# Hypnos_V2_2_24.net
KiCad netlist of a schematic drawn in EAGLE
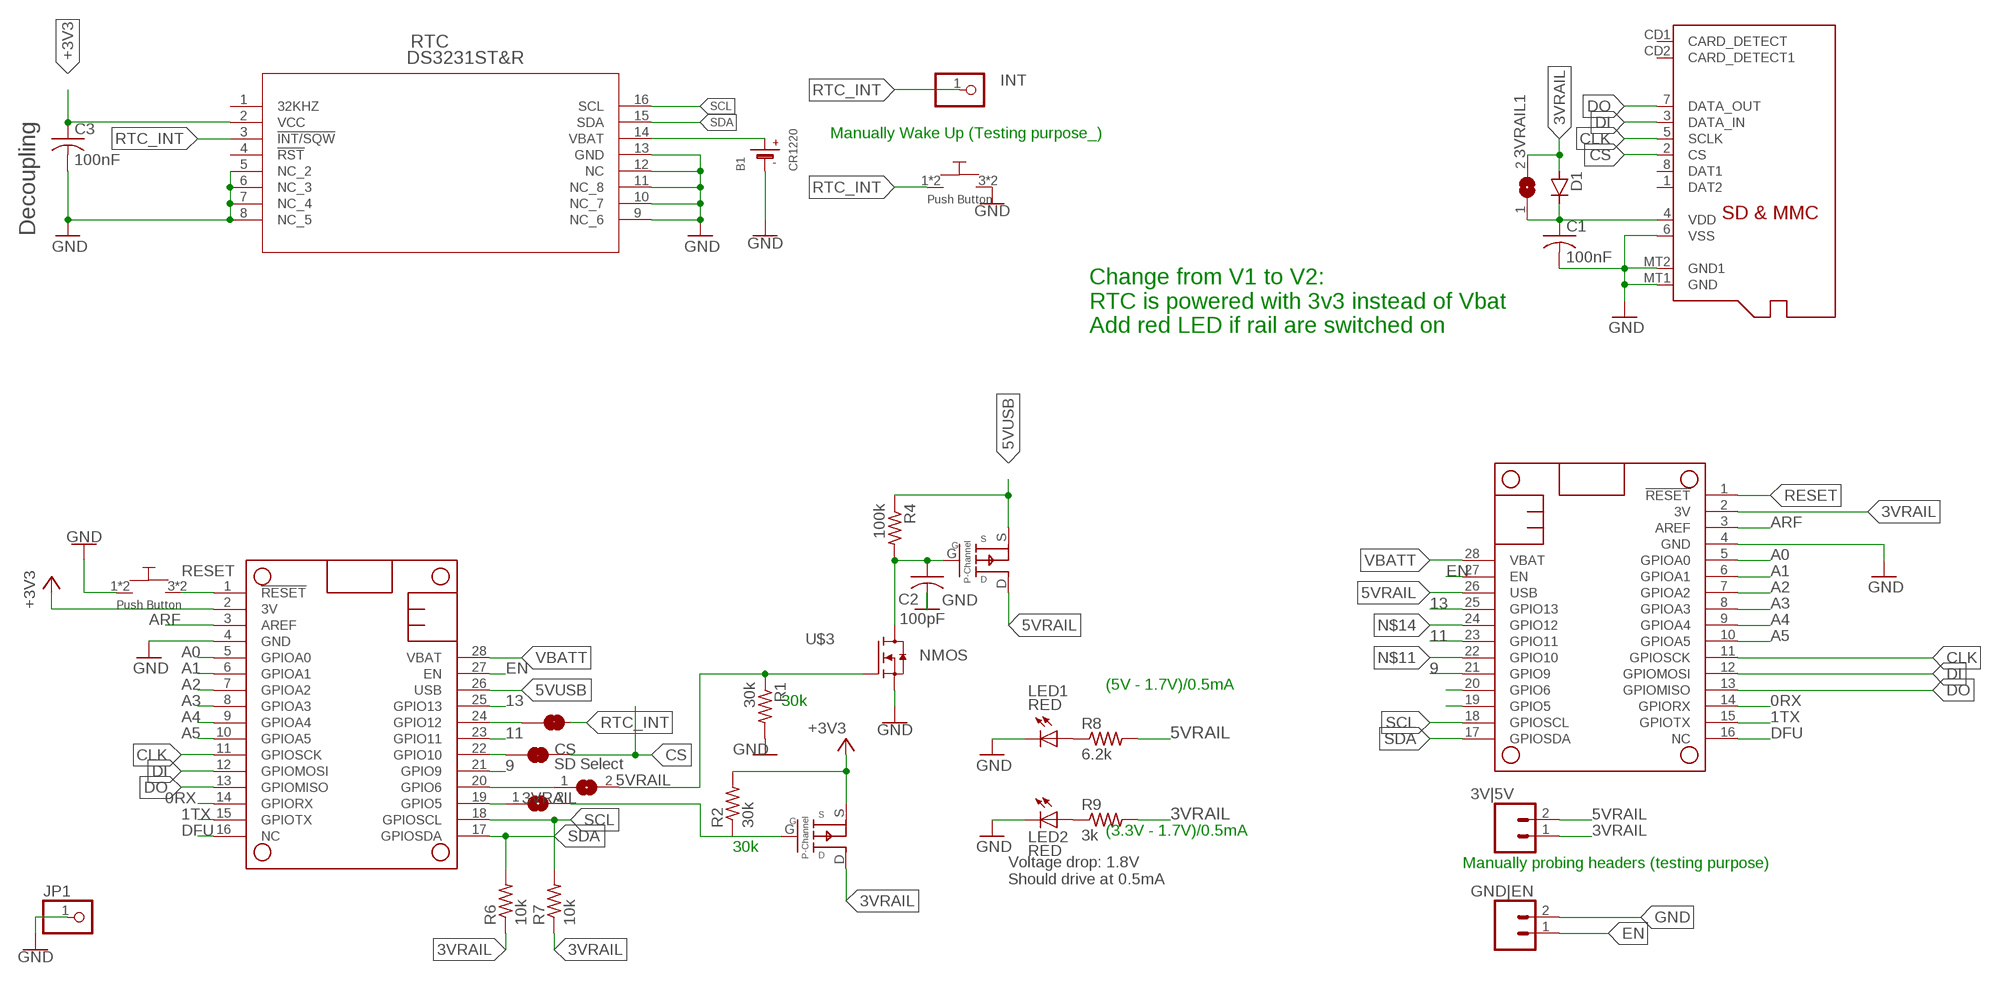
[diagram p0: schematic, sheet 1]

(export (version "E")
  (design (tool "Eeschema 10.0.6"))
  (components
    (comp (ref "3VRAIL")
      (value "SJ")
      (footprint "eagle-import:SJ")
      (libsource (lib "eagle-import") (part "SJ"))
    )
    (comp (ref "3VRAIL1")
      (value "SJ")
      (footprint "eagle-import:SJ")
      (libsource (lib "eagle-import") (part "SJ"))
    )
    (comp (ref "3V|5V")
      (value "CONN_021X02_NO_SILK")
      (footprint "eagle-import:1X02_NO_SILK")
      (libsource (lib "eagle-import") (part "CONN_021X02_NO_SILK"))
    )
    (comp (ref "5VRAIL")
      (value "SJ")
      (footprint "eagle-import:SJ")
      (libsource (lib "eagle-import") (part "SJ"))
    )
    (comp (ref "B1")
      (value "CR1220")
      (footprint "eagle-import:CR1220")
      (libsource (lib "eagle-import") (part "BATTERYCR1220_SMT"))
    )
    (comp (ref "C1")
      (value "100nF")
      (footprint "eagle-import:C1206")
      (libsource (lib "eagle-import") (part "C-USC1206"))
    )
    (comp (ref "C2")
      (value "100pF")
      (footprint "eagle-import:C0805")
      (libsource (lib "eagle-import") (part "C-USC0805"))
    )
    (comp (ref "C3")
      (value "100nF")
      (footprint "eagle-import:C1206")
      (libsource (lib "eagle-import") (part "C-USC1206"))
    )
    (comp (ref "CS")
      (value "SD Select")
      (footprint "eagle-import:SMT-JUMPER_2_NC_TRACE_SILK")
      (libsource (lib "eagle-import") (part "JUMPER-SMT_2_NC_TRACE_SILK"))
    )
    (comp (ref "D1")
      (value "D-SOD123")
      (footprint "eagle-import:SOD123")
      (libsource (lib "eagle-import") (part "D-SOD123"))
    )
    (comp (ref "GND|EN")
      (value "CONN_021X02_NO_SILK")
      (footprint "eagle-import:1X02_NO_SILK")
      (libsource (lib "eagle-import") (part "CONN_021X02_NO_SILK"))
    )
    (comp (ref "INT")
      (value "PINHD-1X1CB")
      (footprint "eagle-import:1X01-CLEANBIG")
      (libsource (lib "eagle-import") (part "PINHD-1X1CB"))
    )
    (comp (ref "JP1")
      (value "PINHD-1X1CB")
      (footprint "eagle-import:1X01-CLEANBIG")
      (libsource (lib "eagle-import") (part "PINHD-1X1CB"))
    )
    (comp (ref "LED1")
      (value "RED")
      (footprint "eagle-import:CHIPLED_0805")
      (libsource (lib "eagle-import") (part "LEDCHIPLED_0805"))
    )
    (comp (ref "LED2")
      (value "RED")
      (footprint "eagle-import:CHIPLED_0805")
      (libsource (lib "eagle-import") (part "LEDCHIPLED_0805"))
    )
    (comp (ref "MICROSD")
      (value "MICROSD")
      (footprint "eagle-import:MICROSD")
      (libsource (lib "eagle-import") (part "MICROSD"))
    )
    (comp (ref "MS1")
      (value "FEATHERWING")
      (footprint "eagle-import:FEATHERWING")
      (libsource (lib "eagle-import") (part "powerboard_FEATHERWING"))
    )
    (comp (ref "MS2")
      (value "FEATHERWING")
      (footprint "eagle-import:FEATHERWING")
      (libsource (lib "eagle-import") (part "FEATHERWING"))
    )
    (comp (ref "PMOS1")
      (value "SSM3J3228R")
      (footprint "eagle-import:SOT-23-3")
      (libsource (lib "eagle-import") (part "SSM3J3228R"))
    )
    (comp (ref "PMOS2")
      (value "SSM3J3228R")
      (footprint "eagle-import:SOT-23-3")
      (libsource (lib "eagle-import") (part "SSM3J3228R"))
    )
    (comp (ref "R1")
      (value "30k")
      (footprint "eagle-import:RES_1206")
      (fields
        (field (name "DIGIKEY_PART_NUMBER") "WSLP-.05TR-ND")
        (field (name "MANUFACTURER") "Vishay Dale")
        (field (name "MPN") "WSLP1206R0500FEA")
        (field (name "CREATED_BY") "PCBLayout.com")
      )
      (libsource (lib "eagle-import") (part "WSLP1206R0500FEA"))
    )
    (comp (ref "R2")
      (value "30k")
      (footprint "eagle-import:RES_1206")
      (fields
        (field (name "DIGIKEY_PART_NUMBER") "WSLP-.05TR-ND")
        (field (name "MANUFACTURER") "Vishay Dale")
        (field (name "MPN") "WSLP1206R0500FEA")
        (field (name "CREATED_BY") "PCBLayout.com")
      )
      (libsource (lib "eagle-import") (part "WSLP1206R0500FEA"))
    )
    (comp (ref "R4")
      (value "100k")
      (footprint "eagle-import:RES_1206")
      (fields
        (field (name "DIGIKEY_PART_NUMBER") "WSLP-.05TR-ND")
        (field (name "MANUFACTURER") "Vishay Dale")
        (field (name "MPN") "WSLP1206R0500FEA")
        (field (name "CREATED_BY") "PCBLayout.com")
      )
      (libsource (lib "eagle-import") (part "WSLP1206R0500FEA"))
    )
    (comp (ref "R6")
      (value "10k")
      (footprint "eagle-import:RES_1206")
      (fields
        (field (name "DIGIKEY_PART_NUMBER") "WSLP-.05TR-ND")
        (field (name "MANUFACTURER") "Vishay Dale")
        (field (name "MPN") "WSLP1206R0500FEA")
        (field (name "CREATED_BY") "PCBLayout.com")
      )
      (libsource (lib "eagle-import") (part "WSLP1206R0500FEA"))
    )
    (comp (ref "R7")
      (value "10k")
      (footprint "eagle-import:RES_1206")
      (fields
        (field (name "DIGIKEY_PART_NUMBER") "WSLP-.05TR-ND")
        (field (name "MANUFACTURER") "Vishay Dale")
        (field (name "MPN") "WSLP1206R0500FEA")
        (field (name "CREATED_BY") "PCBLayout.com")
      )
      (libsource (lib "eagle-import") (part "WSLP1206R0500FEA"))
    )
    (comp (ref "R8")
      (value "6.2k")
      (footprint "eagle-import:RES_1206")
      (fields
        (field (name "DIGIKEY_PART_NUMBER") "WSLP-.05TR-ND")
        (field (name "MANUFACTURER") "Vishay Dale")
        (field (name "MPN") "WSLP1206R0500FEA")
        (field (name "CREATED_BY") "PCBLayout.com")
      )
      (libsource (lib "eagle-import") (part "WSLP1206R0500FEA"))
    )
    (comp (ref "R9")
      (value "3k")
      (footprint "eagle-import:RES_1206")
      (fields
        (field (name "DIGIKEY_PART_NUMBER") "WSLP-.05TR-ND")
        (field (name "MANUFACTURER") "Vishay Dale")
        (field (name "MPN") "WSLP1206R0500FEA")
        (field (name "CREATED_BY") "PCBLayout.com")
      )
      (libsource (lib "eagle-import") (part "WSLP1206R0500FEA"))
    )
    (comp (ref "RTC")
      (value "DS3231ST&R")
      (footprint "eagle-import:21-0042B_16")
      (fields (field (name "MANUFACTURER_PART_NUMBER") "DS3231S#T&R"))
      (libsource (lib "eagle-import") (part "DS3231ST&R"))
    )
    (comp (ref "RTC_INT")
      (value "JUMPER-SMT_2_NC_TRACE_SILK")
      (footprint "eagle-import:SMT-JUMPER_2_NC_TRACE_SILK")
      (libsource (lib "eagle-import") (part "JUMPER-SMT_2_NC_TRACE_SILK"))
    )
    (comp (ref "U$1")
      (value "PUSH_BUTTON")
      (footprint "eagle-import:PUSHBUTTON_SMD")
      (libsource (lib "eagle-import") (part "PUSH_BUTTON"))
    )
    (comp (ref "U$2")
      (value "PUSH_BUTTON")
      (footprint "eagle-import:PUSHBUTTON_SMD")
      (libsource (lib "eagle-import") (part "PUSH_BUTTON"))
    )
    (comp (ref "U$3")
      (value "NMOS")
      (footprint "eagle-import:SOT23-S")
      (libsource (lib "eagle-import") (part "NMOS"))
    )
  )
  (nets
    (net (code "1") (name "+3V3") (class "Default")
      (node (ref "C3") (pin "1") (pinfunction "1_1") (pintype "passive"))
      (node (ref "MS2") (pin "2") (pinfunction "3V_2") (pintype "power_in"))
      (node (ref "PMOS2") (pin "S") (pinfunction "S_S") (pintype "bidirectional"))
      (node (ref "R2") (pin "2") (pinfunction "2_2") (pintype "passive"))
      (node (ref "RTC") (pin "2") (pinfunction "VCC_2") (pintype "power_in"))
    )
    (net (code "2") (name "/0RX") (class "Default")
      (node (ref "MS1") (pin "14") (pinfunction "GPIORX_14") (pintype "bidirectional"))
      (node (ref "MS2") (pin "14") (pinfunction "GPIORX_14") (pintype "bidirectional"))
    )
    (net (code "3") (name "/1TX") (class "Default")
      (node (ref "MS1") (pin "15") (pinfunction "GPIOTX_15") (pintype "bidirectional"))
      (node (ref "MS2") (pin "15") (pinfunction "GPIOTX_15") (pintype "bidirectional"))
    )
    (net (code "4") (name "/9") (class "Default")
      (node (ref "MS1") (pin "21") (pinfunction "GPIO9_21") (pintype "bidirectional"))
      (node (ref "MS2") (pin "21") (pinfunction "GPIO9_21") (pintype "bidirectional"))
    )
    (net (code "5") (name "/11") (class "Default")
      (node (ref "MS1") (pin "23") (pinfunction "GPIO11_23") (pintype "bidirectional"))
      (node (ref "MS2") (pin "23") (pinfunction "GPIO11_23") (pintype "bidirectional"))
    )
    (net (code "6") (name "/13") (class "Default")
      (node (ref "MS1") (pin "25") (pinfunction "GPIO13_25") (pintype "bidirectional"))
      (node (ref "MS2") (pin "25") (pinfunction "GPIO13_25") (pintype "bidirectional"))
    )
    (net (code "7") (name "/A0") (class "Default")
      (node (ref "MS1") (pin "5") (pinfunction "GPIOA0_5") (pintype "bidirectional"))
      (node (ref "MS2") (pin "5") (pinfunction "GPIOA0_5") (pintype "bidirectional"))
    )
    (net (code "8") (name "/A1") (class "Default")
      (node (ref "MS1") (pin "6") (pinfunction "GPIOA1_6") (pintype "bidirectional"))
      (node (ref "MS2") (pin "6") (pinfunction "GPIOA1_6") (pintype "bidirectional"))
    )
    (net (code "9") (name "/A2") (class "Default")
      (node (ref "MS1") (pin "7") (pinfunction "GPIOA2_7") (pintype "bidirectional"))
      (node (ref "MS2") (pin "7") (pinfunction "GPIOA2_7") (pintype "bidirectional"))
    )
    (net (code "10") (name "/A3") (class "Default")
      (node (ref "MS1") (pin "8") (pinfunction "GPIOA3_8") (pintype "bidirectional"))
      (node (ref "MS2") (pin "8") (pinfunction "GPIOA3_8") (pintype "bidirectional"))
    )
    (net (code "11") (name "/A4") (class "Default")
      (node (ref "MS1") (pin "9") (pinfunction "GPIOA4_9") (pintype "bidirectional"))
      (node (ref "MS2") (pin "9") (pinfunction "GPIOA4_9") (pintype "bidirectional"))
    )
    (net (code "12") (name "/A5") (class "Default")
      (node (ref "MS1") (pin "10") (pinfunction "GPIOA5_10") (pintype "bidirectional"))
      (node (ref "MS2") (pin "10") (pinfunction "GPIOA5_10") (pintype "bidirectional"))
    )
    (net (code "13") (name "/ARF") (class "Default")
      (node (ref "MS1") (pin "3") (pinfunction "AREF_3") (pintype "passive"))
      (node (ref "MS2") (pin "3") (pinfunction "AREF_3") (pintype "passive"))
    )
    (net (code "14") (name "/DFU") (class "Default")
      (node (ref "MS1") (pin "16") (pinfunction "NC_16") (pintype "passive"))
      (node (ref "MS2") (pin "16") (pinfunction "NC_16") (pintype "passive"))
    )
    (net (code "15") (name "3VRAIL") (class "Default")
      (node (ref "3VRAIL1") (pin "2") (pinfunction "2_2") (pintype "passive"))
      (node (ref "3V|5V") (pin "1") (pinfunction "1_1") (pintype "passive"))
      (node (ref "D1") (pin "2") (pinfunction "A_2") (pintype "passive"))
      (node (ref "MS1") (pin "2") (pinfunction "3V_2") (pintype "power_in"))
      (node (ref "PMOS2") (pin "D") (pinfunction "D_D") (pintype "bidirectional"))
      (node (ref "R6") (pin "1") (pinfunction "1_1") (pintype "passive"))
      (node (ref "R7") (pin "1") (pinfunction "1_1") (pintype "passive"))
      (node (ref "R9") (pin "2") (pinfunction "2_2") (pintype "passive"))
    )
    (net (code "16") (name "5VRAIL") (class "Default")
      (node (ref "3V|5V") (pin "2") (pinfunction "2_2") (pintype "passive"))
      (node (ref "MS1") (pin "26") (pinfunction "USB_26") (pintype "power_in"))
      (node (ref "PMOS1") (pin "D") (pinfunction "D_D") (pintype "bidirectional"))
      (node (ref "R8") (pin "2") (pinfunction "2_2") (pintype "passive"))
    )
    (net (code "17") (name "5VUSB") (class "Default")
      (node (ref "MS2") (pin "26") (pinfunction "USB_26") (pintype "power_in"))
      (node (ref "PMOS1") (pin "S") (pinfunction "S_S") (pintype "bidirectional"))
      (node (ref "R4") (pin "1") (pinfunction "1_1") (pintype "passive"))
    )
    (net (code "18") (name "CLK") (class "Default")
      (node (ref "MICROSD") (pin "5") (pinfunction "SCLK_5") (pintype "input"))
      (node (ref "MS1") (pin "11") (pinfunction "GPIOSCK_11") (pintype "bidirectional"))
      (node (ref "MS2") (pin "11") (pinfunction "GPIOSCK_11") (pintype "bidirectional"))
    )
    (net (code "19") (name "CS") (class "Default")
      (node (ref "CS") (pin "2") (pinfunction "2_2") (pintype "passive"))
      (node (ref "MICROSD") (pin "2") (pinfunction "CS_2") (pintype "input"))
    )
    (net (code "20") (name "DI") (class "Default")
      (node (ref "MICROSD") (pin "3") (pinfunction "DATA_IN_3") (pintype "input"))
      (node (ref "MS1") (pin "12") (pinfunction "GPIOMOSI_12") (pintype "bidirectional"))
      (node (ref "MS2") (pin "12") (pinfunction "GPIOMOSI_12") (pintype "bidirectional"))
    )
    (net (code "21") (name "DO") (class "Default")
      (node (ref "MICROSD") (pin "7") (pinfunction "DATA_OUT_7") (pintype "output"))
      (node (ref "MS1") (pin "13") (pinfunction "GPIOMISO_13") (pintype "bidirectional"))
      (node (ref "MS2") (pin "13") (pinfunction "GPIOMISO_13") (pintype "bidirectional"))
    )
    (net (code "22") (name "EN") (class "Default")
      (node (ref "GND|EN") (pin "1") (pinfunction "1_1") (pintype "passive"))
      (node (ref "MS1") (pin "27") (pinfunction "EN_27") (pintype "passive"))
      (node (ref "MS2") (pin "27") (pinfunction "EN_27") (pintype "passive"))
    )
    (net (code "23") (name "GND") (class "Default")
      (node (ref "B1") (pin "-") (pinfunction "-_-") (pintype "passive"))
      (node (ref "C1") (pin "2") (pinfunction "2_2") (pintype "passive"))
      (node (ref "C2") (pin "2") (pinfunction "2_2") (pintype "passive"))
      (node (ref "C3") (pin "2") (pinfunction "2_2") (pintype "passive"))
      (node (ref "GND|EN") (pin "2") (pinfunction "2_2") (pintype "passive"))
      (node (ref "JP1") (pin "1") (pinfunction "1_1") (pintype "passive"))
      (node (ref "LED1") (pin "C") (pinfunction "C_C") (pintype "passive"))
      (node (ref "LED2") (pin "C") (pinfunction "C_C") (pintype "passive"))
      (node (ref "MICROSD") (pin "6") (pinfunction "VSS_6") (pintype "power_in"))
      (node (ref "MICROSD") (pin "MT1") (pinfunction "GND_MT1") (pintype "power_in"))
      (node (ref "MICROSD") (pin "MT2") (pinfunction "GND1_MT2") (pintype "power_in"))
      (node (ref "MS1") (pin "4") (pinfunction "GND_4") (pintype "power_in"))
      (node (ref "MS2") (pin "4") (pinfunction "GND_4") (pintype "power_in"))
      (node (ref "R1") (pin "2") (pinfunction "2_2") (pintype "passive"))
      (node (ref "RTC") (pin "10") (pinfunction "NC_7_10") (pintype "passive"))
      (node (ref "RTC") (pin "11") (pinfunction "NC_8_11") (pintype "passive"))
      (node (ref "RTC") (pin "12") (pinfunction "NC_12") (pintype "passive"))
      (node (ref "RTC") (pin "13") (pinfunction "GND_13") (pintype "power_in"))
      (node (ref "RTC") (pin "5") (pinfunction "NC_2_5") (pintype "passive"))
      (node (ref "RTC") (pin "6") (pinfunction "NC_3_6") (pintype "passive"))
      (node (ref "RTC") (pin "7") (pinfunction "NC_4_7") (pintype "passive"))
      (node (ref "RTC") (pin "8") (pinfunction "NC_5_8") (pintype "passive"))
      (node (ref "RTC") (pin "9") (pinfunction "NC_6_9") (pintype "passive"))
      (node (ref "U$1") (pin "1") (pinfunction "P$1_1") (pintype "bidirectional"))
      (node (ref "U$1") (pin "2") (pinfunction "P$1_2") (pintype "bidirectional"))
      (node (ref "U$2") (pin "3") (pinfunction "P$2_3") (pintype "bidirectional"))
      (node (ref "U$2") (pin "4") (pinfunction "P$2_4") (pintype "bidirectional"))
      (node (ref "U$3") (pin "2") (pinfunction "S_2") (pintype "passive"))
    )
    (net (code "24") (name "N$11") (class "Default")
      (node (ref "CS") (pin "1") (pinfunction "1_1") (pintype "passive"))
      (node (ref "MS1") (pin "22") (pinfunction "GPIO10_22") (pintype "bidirectional"))
      (node (ref "MS2") (pin "22") (pinfunction "GPIO10_22") (pintype "bidirectional"))
    )
    (net (code "25") (name "N$14") (class "Default")
      (node (ref "MS1") (pin "24") (pinfunction "GPIO12_24") (pintype "bidirectional"))
      (node (ref "MS2") (pin "24") (pinfunction "GPIO12_24") (pintype "bidirectional"))
      (node (ref "RTC_INT") (pin "1") (pinfunction "1_1") (pintype "passive"))
    )
    (net (code "26") (name "Net-(3VRAIL-Pad2)") (class "Default")
      (node (ref "3VRAIL") (pin "2") (pinfunction "2_2") (pintype "passive"))
      (node (ref "PMOS2") (pin "G") (pinfunction "G_G") (pintype "bidirectional"))
      (node (ref "R2") (pin "1") (pinfunction "1_1") (pintype "passive"))
    )
    (net (code "27") (name "Net-(B1-+)") (class "Default")
      (node (ref "B1") (pin "+$1") (pinfunction "+_+$1") (pintype "passive"))
      (node (ref "RTC") (pin "14") (pinfunction "VBAT_14") (pintype "power_in"))
    )
    (net (code "28") (name "Net-(D1-C)") (class "Default")
      (node (ref "3VRAIL1") (pin "1") (pinfunction "1_1") (pintype "passive"))
      (node (ref "C1") (pin "1") (pinfunction "1_1") (pintype "passive"))
      (node (ref "D1") (pin "1") (pinfunction "C_1") (pintype "passive"))
      (node (ref "MICROSD") (pin "4") (pinfunction "VDD_4") (pintype "power_in"))
    )
    (net (code "29") (name "Net-(LED1-PadA)") (class "Default")
      (node (ref "LED1") (pin "A") (pinfunction "A_A") (pintype "passive"))
      (node (ref "R8") (pin "1") (pinfunction "1_1") (pintype "passive"))
    )
    (net (code "30") (name "Net-(LED2-PadA)") (class "Default")
      (node (ref "LED2") (pin "A") (pinfunction "A_A") (pintype "passive"))
      (node (ref "R9") (pin "1") (pinfunction "1_1") (pintype "passive"))
    )
    (net (code "31") (name "Net-(MS2-GPIO5)") (class "Default")
      (node (ref "3VRAIL") (pin "1") (pinfunction "1_1") (pintype "passive"))
      (node (ref "MS2") (pin "19") (pinfunction "GPIO5_19") (pintype "bidirectional"))
    )
    (net (code "32") (name "Net-(MS2-GPIO6)") (class "Default")
      (node (ref "5VRAIL") (pin "1") (pinfunction "1_1") (pintype "passive"))
      (node (ref "MS2") (pin "20") (pinfunction "GPIO6_20") (pintype "bidirectional"))
    )
    (net (code "33") (name "Net-(U$3-D)") (class "Default")
      (node (ref "C2") (pin "1") (pinfunction "1_1") (pintype "passive"))
      (node (ref "PMOS1") (pin "G") (pinfunction "G_G") (pintype "bidirectional"))
      (node (ref "R4") (pin "2") (pinfunction "2_2") (pintype "passive"))
      (node (ref "U$3") (pin "3") (pinfunction "D_3") (pintype "passive"))
    )
    (net (code "34") (name "Net-(U$3-G)") (class "Default")
      (node (ref "5VRAIL") (pin "2") (pinfunction "2_2") (pintype "passive"))
      (node (ref "R1") (pin "1") (pinfunction "1_1") (pintype "passive"))
      (node (ref "U$3") (pin "1") (pinfunction "G_1") (pintype "passive"))
    )
    (net (code "35") (name "RESET") (class "Default")
      (node (ref "MS1") (pin "1") (pinfunction "~{RESET}_1") (pintype "input"))
      (node (ref "MS2") (pin "1") (pinfunction "~{RESET}_1") (pintype "input"))
      (node (ref "U$1") (pin "3") (pinfunction "P$2_3") (pintype "bidirectional"))
      (node (ref "U$1") (pin "4") (pinfunction "P$2_4") (pintype "bidirectional"))
    )
    (net (code "36") (name "RTC_INT") (class "Default")
      (node (ref "INT") (pin "1") (pinfunction "1_1") (pintype "passive"))
      (node (ref "RTC") (pin "3") (pinfunction "~{INT/SQW}_3") (pintype "passive"))
      (node (ref "RTC_INT") (pin "2") (pinfunction "2_2") (pintype "passive"))
      (node (ref "U$2") (pin "1") (pinfunction "P$1_1") (pintype "bidirectional"))
      (node (ref "U$2") (pin "2") (pinfunction "P$1_2") (pintype "bidirectional"))
    )
    (net (code "37") (name "SCL") (class "Default")
      (node (ref "MS1") (pin "18") (pinfunction "GPIOSCL_18") (pintype "bidirectional"))
      (node (ref "MS2") (pin "18") (pinfunction "GPIOSCL_18") (pintype "bidirectional"))
      (node (ref "R7") (pin "2") (pinfunction "2_2") (pintype "passive"))
      (node (ref "RTC") (pin "16") (pinfunction "SCL_16") (pintype "passive"))
    )
    (net (code "38") (name "SDA") (class "Default")
      (node (ref "MS1") (pin "17") (pinfunction "GPIOSDA_17") (pintype "bidirectional"))
      (node (ref "MS2") (pin "17") (pinfunction "GPIOSDA_17") (pintype "bidirectional"))
      (node (ref "R6") (pin "2") (pinfunction "2_2") (pintype "passive"))
      (node (ref "RTC") (pin "15") (pinfunction "SDA_15") (pintype "passive"))
    )
    (net (code "39") (name "VBATT") (class "Default")
      (node (ref "MS1") (pin "28") (pinfunction "VBAT_28") (pintype "power_in"))
      (node (ref "MS2") (pin "28") (pinfunction "VBAT_28") (pintype "power_in"))
    )
    (net (code "40") (name "unconnected-(MICROSD-CARD_DETECT-PadCD1)") (class "Default")
      (node (ref "MICROSD") (pin "CD1") (pinfunction "CARD_DETECT_CD1") (pintype "passive"))
    )
    (net (code "41") (name "unconnected-(MICROSD-CARD_DETECT1-PadCD2)") (class "Default")
      (node (ref "MICROSD") (pin "CD2") (pinfunction "CARD_DETECT1_CD2") (pintype "passive"))
    )
    (net (code "42") (name "unconnected-(MICROSD-DAT1-Pad8)") (class "Default")
      (node (ref "MICROSD") (pin "8") (pinfunction "DAT1_8") (pintype "bidirectional"))
    )
    (net (code "43") (name "unconnected-(MICROSD-DAT2-Pad1)") (class "Default")
      (node (ref "MICROSD") (pin "1") (pinfunction "DAT2_1") (pintype "bidirectional"))
    )
    (net (code "44") (name "unconnected-(MS1-GPIO5-Pad19)") (class "Default")
      (node (ref "MS1") (pin "19") (pinfunction "GPIO5_19") (pintype "bidirectional"))
    )
    (net (code "45") (name "unconnected-(MS1-GPIO6-Pad20)") (class "Default")
      (node (ref "MS1") (pin "20") (pinfunction "GPIO6_20") (pintype "bidirectional"))
    )
    (net (code "46") (name "unconnected-(RTC-32KHZ-Pad1)") (class "Default")
      (node (ref "RTC") (pin "1") (pinfunction "32KHZ_1") (pintype "passive"))
    )
    (net (code "47") (name "unconnected-(RTC-~{RST}-Pad4)") (class "Default")
      (node (ref "RTC") (pin "4") (pinfunction "~{RST}_4") (pintype "passive"))
    )
  )
)
